# OpenProg-18F2550-new.net
KiCad netlist of a schematic drawn in EAGLE
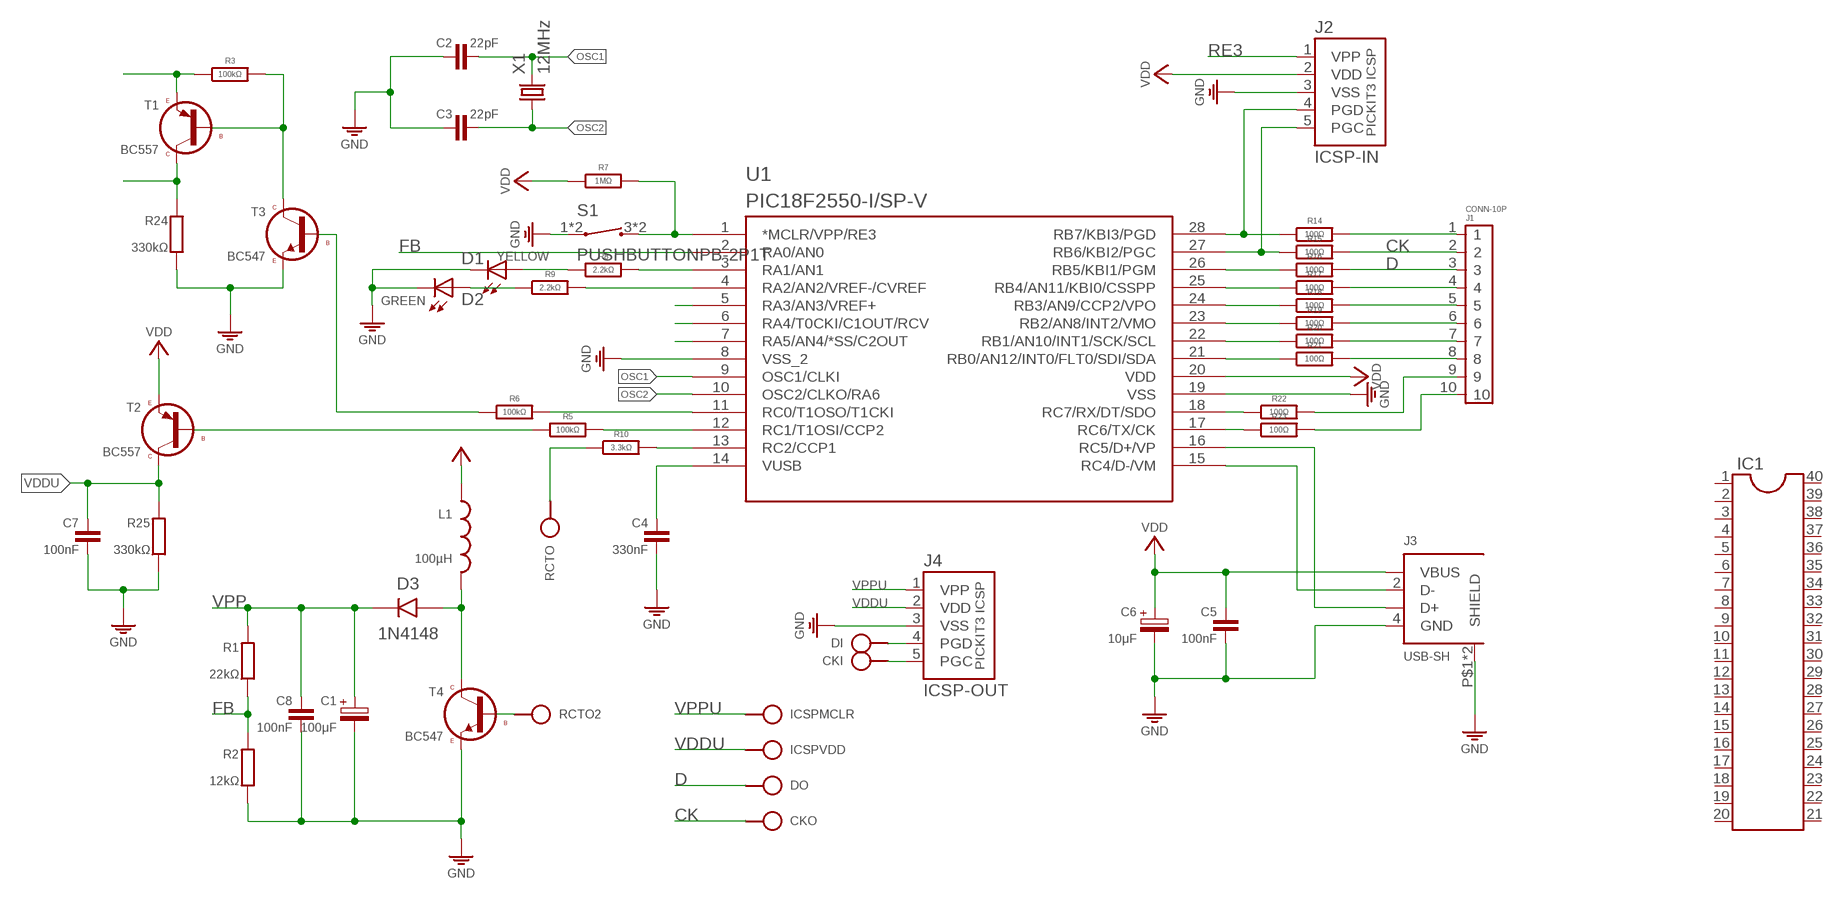
[diagram p0: schematic, sheet 1]

(export (version "E")
  (design (tool "Eeschema 10.0.6"))
  (components
    (comp (ref "C1")
      (value "100μF")
      (footprint "eagle-import:E2,5-5_V")
      (libsource (lib "eagle-import") (part "CPOLE2,5-5/V"))
    )
    (comp (ref "C2")
      (value "22pF")
      (footprint "eagle-import:C025-015X024")
      (libsource (lib "eagle-import") (part "C-H025-015X024"))
    )
    (comp (ref "C3")
      (value "22pF")
      (footprint "eagle-import:C025-015X024")
      (libsource (lib "eagle-import") (part "C-H025-015X024"))
    )
    (comp (ref "C4")
      (value "330nF")
      (footprint "eagle-import:C050-030X075")
      (libsource (lib "eagle-import") (part "C050-030X075"))
    )
    (comp (ref "C5")
      (value "100nF")
      (footprint "eagle-import:C025-015X024")
      (libsource (lib "eagle-import") (part "C025-015X024"))
    )
    (comp (ref "C6")
      (value "10μF")
      (footprint "eagle-import:E2,5-5")
      (libsource (lib "eagle-import") (part "CPOLE2.5-5"))
    )
    (comp (ref "C7")
      (value "100nF")
      (footprint "eagle-import:C025-015X024")
      (libsource (lib "eagle-import") (part "C025-015X024"))
    )
    (comp (ref "C8")
      (value "100nF")
      (footprint "eagle-import:C025-015X024")
      (libsource (lib "eagle-import") (part "C025-015X024"))
    )
    (comp (ref "CKI")
      (value "HPORT")
      (footprint "eagle-import:SPAD")
      (libsource (lib "eagle-import") (part "HPORT"))
    )
    (comp (ref "CKO")
      (value "HPORT")
      (footprint "eagle-import:SPAD")
      (libsource (lib "eagle-import") (part "HPORT"))
    )
    (comp (ref "D1")
      (value "YELLOW")
      (footprint "eagle-import:LED_3MM")
      (libsource (lib "eagle-import") (part "LED-3MM"))
    )
    (comp (ref "D2")
      (value "GREEN")
      (footprint "eagle-import:LED_3MM")
      (libsource (lib "eagle-import") (part "LED-3MM"))
    )
    (comp (ref "D3")
      (value "1N4148")
      (footprint "eagle-import:DO34-7")
      (libsource (lib "eagle-import") (part "1N4148-HDO34-7"))
    )
    (comp (ref "DI")
      (value "HPORT")
      (footprint "eagle-import:SPAD")
      (libsource (lib "eagle-import") (part "HPORT"))
    )
    (comp (ref "DO")
      (value "HPORT")
      (footprint "eagle-import:SPAD")
      (libsource (lib "eagle-import") (part "HPORT"))
    )
    (comp (ref "IC1")
      (value "DIL40")
      (footprint "eagle-import:DIL40")
      (libsource (lib "eagle-import") (part "DIL40"))
    )
    (comp (ref "ICSPMCLR")
      (value "HPORT")
      (footprint "eagle-import:SPAD")
      (libsource (lib "eagle-import") (part "HPORT"))
    )
    (comp (ref "ICSPVDD")
      (value "HPORT")
      (footprint "eagle-import:SPAD")
      (libsource (lib "eagle-import") (part "HPORT"))
    )
    (comp (ref "J1")
      (value "CONN-10P")
      (footprint "eagle-import:CONN-10P")
      (libsource (lib "eagle-import") (part "CONN-10P"))
    )
    (comp (ref "J2")
      (value "ICSP-IN")
      (footprint "eagle-import:PIC-PK3")
      (libsource (lib "eagle-import") (part "PICKIT3-ICSP-PK3"))
    )
    (comp (ref "J3")
      (value "USB-SH")
      (footprint "eagle-import:USB-B-PRINT")
      (libsource (lib "eagle-import") (part "USB-SH"))
    )
    (comp (ref "J4")
      (value "ICSP-OUT")
      (footprint "eagle-import:PIC-PK3")
      (libsource (lib "eagle-import") (part "PICKIT3-ICSP-PK3"))
    )
    (comp (ref "L1")
      (value "100µH")
      (footprint "eagle-import:L-03_10V")
      (libsource (lib "eagle-import") (part "L02/10"))
    )
    (comp (ref "R1")
      (value "22kΩ")
      (footprint "eagle-import:0204_10-V")
      (libsource (lib "eagle-import") (part "R0204/10-V"))
    )
    (comp (ref "R2")
      (value "12kΩ")
      (footprint "eagle-import:0204_10-V")
      (libsource (lib "eagle-import") (part "R0204/10-V"))
    )
    (comp (ref "R3")
      (value "100kΩ")
      (footprint "eagle-import:0204_2")
      (libsource (lib "eagle-import") (part "R-H0204/2"))
    )
    (comp (ref "R5")
      (value "100kΩ")
      (footprint "eagle-import:0204_10")
      (libsource (lib "eagle-import") (part "R-H0204/10"))
    )
    (comp (ref "R6")
      (value "100kΩ")
      (footprint "eagle-import:0204_10")
      (libsource (lib "eagle-import") (part "R-H0204/10"))
    )
    (comp (ref "R7")
      (value "1MΩ")
      (footprint "eagle-import:0204_10-V")
      (libsource (lib "eagle-import") (part "R-H0204/10-V"))
    )
    (comp (ref "R8")
      (value "2.2kΩ")
      (footprint "eagle-import:0204_10")
      (libsource (lib "eagle-import") (part "R-H0204/10"))
    )
    (comp (ref "R9")
      (value "2.2kΩ")
      (footprint "eagle-import:0204_10")
      (libsource (lib "eagle-import") (part "R-H0204/10"))
    )
    (comp (ref "R10")
      (value "3.3kΩ")
      (footprint "eagle-import:0204_10")
      (libsource (lib "eagle-import") (part "R-H0204/10"))
    )
    (comp (ref "R14")
      (value "100Ω")
      (footprint "eagle-import:0204_10")
      (libsource (lib "eagle-import") (part "R-H0204/10"))
    )
    (comp (ref "R15")
      (value "100Ω")
      (footprint "eagle-import:0204_10")
      (libsource (lib "eagle-import") (part "R-H0204/10"))
    )
    (comp (ref "R16")
      (value "100Ω")
      (footprint "eagle-import:0204_10")
      (libsource (lib "eagle-import") (part "R-H0204/10"))
    )
    (comp (ref "R17")
      (value "100Ω")
      (footprint "eagle-import:0204_10")
      (libsource (lib "eagle-import") (part "R-H0204/10"))
    )
    (comp (ref "R18")
      (value "100Ω")
      (footprint "eagle-import:0204_10")
      (libsource (lib "eagle-import") (part "R-H0204/10"))
    )
    (comp (ref "R19")
      (value "100Ω")
      (footprint "eagle-import:0204_10")
      (libsource (lib "eagle-import") (part "R-H0204/10"))
    )
    (comp (ref "R20")
      (value "100Ω")
      (footprint "eagle-import:0204_10")
      (libsource (lib "eagle-import") (part "R-H0204/10"))
    )
    (comp (ref "R21")
      (value "100Ω")
      (footprint "eagle-import:0204_10")
      (libsource (lib "eagle-import") (part "R-H0204/10"))
    )
    (comp (ref "R22")
      (value "100Ω")
      (footprint "eagle-import:0204_10")
      (libsource (lib "eagle-import") (part "R-H0204/10"))
    )
    (comp (ref "R23")
      (value "100Ω")
      (footprint "eagle-import:0204_10")
      (libsource (lib "eagle-import") (part "R-H0204/10"))
    )
    (comp (ref "R24")
      (value "330kΩ")
      (footprint "eagle-import:0204_10-V")
      (libsource (lib "eagle-import") (part "R0204/10-V"))
    )
    (comp (ref "R25")
      (value "330kΩ")
      (footprint "eagle-import:0204_10-V")
      (libsource (lib "eagle-import") (part "R0204/10-V"))
    )
    (comp (ref "RCTO")
      (value "HPORT")
      (footprint "eagle-import:SPAD")
      (libsource (lib "eagle-import") (part "HPORT"))
    )
    (comp (ref "RCTO2")
      (value "HPORT")
      (footprint "eagle-import:SPAD")
      (libsource (lib "eagle-import") (part "HPORT"))
    )
    (comp (ref "S1")
      (value "PUSHBUTTONPB-2P1T")
      (footprint "eagle-import:PB-2P1T")
      (libsource (lib "eagle-import") (part "PUSHBUTTONPB-2P1T"))
    )
    (comp (ref "T1")
      (value "BC557")
      (footprint "eagle-import:TO92-CBE")
      (libsource (lib "eagle-import") (part "BC557CBE"))
    )
    (comp (ref "T2")
      (value "BC557")
      (footprint "eagle-import:TO92-CBE")
      (libsource (lib "eagle-import") (part "BC557CBE"))
    )
    (comp (ref "T3")
      (value "BC547")
      (footprint "eagle-import:TO92")
      (libsource (lib "eagle-import") (part "BC547"))
    )
    (comp (ref "T4")
      (value "BC547")
      (footprint "eagle-import:TO92")
      (libsource (lib "eagle-import") (part "BC547"))
    )
    (comp (ref "U1")
      (value "PIC18F2550-I/SP-V")
      (footprint "eagle-import:DIL28-3_V")
      (libsource (lib "eagle-import") (part "PIC18F2550-I/SP-V"))
    )
    (comp (ref "X1")
      (value "12MHz")
      (footprint "eagle-import:HC49")
      (libsource (lib "eagle-import") (part "CRYSTALHC49"))
    )
  )
  (nets
    (net (code "1") (name "/CK") (class "Default")
      (node (ref "CKO") (pin "1") (pinfunction "P$1_1") (pintype "passive"))
      (node (ref "J1") (pin "2") (pinfunction "2_2") (pintype "passive"))
      (node (ref "R15") (pin "2") (pinfunction "2_2") (pintype "passive"))
    )
    (net (code "2") (name "/D") (class "Default")
      (node (ref "DO") (pin "1") (pinfunction "P$1_1") (pintype "passive"))
      (node (ref "J1") (pin "3") (pinfunction "3_3") (pintype "passive"))
      (node (ref "R16") (pin "2") (pinfunction "2_2") (pintype "passive"))
    )
    (net (code "3") (name "/FB") (class "Default")
      (node (ref "R1") (pin "2") (pinfunction "1_2") (pintype "passive"))
      (node (ref "R2") (pin "1") (pinfunction "2_1") (pintype "passive"))
      (node (ref "U1") (pin "2") (pinfunction "RA0/AN0_2") (pintype "passive"))
    )
    (net (code "4") (name "/RE3") (class "Default")
      (node (ref "J2") (pin "1") (pinfunction "VPP_1") (pintype "passive"))
      (node (ref "R7") (pin "2") (pinfunction "2_2") (pintype "passive"))
      (node (ref "S1") (pin "3") (pinfunction "2_3") (pintype "passive"))
      (node (ref "S1") (pin "4") (pinfunction "2_4") (pintype "passive"))
      (node (ref "U1") (pin "1") (pinfunction "*MCLR/VPP/RE3_1") (pintype "passive"))
    )
    (net (code "5") (name "/VPP") (class "Default")
      (node (ref "C1") (pin "+") (pinfunction "+_+") (pintype "passive"))
      (node (ref "C8") (pin "1") (pinfunction "1_1") (pintype "passive"))
      (node (ref "D3") (pin "C") (pinfunction "C_C") (pintype "passive"))
      (node (ref "R1") (pin "1") (pinfunction "2_1") (pintype "passive"))
      (node (ref "R3") (pin "1") (pinfunction "1_1") (pintype "passive"))
      (node (ref "T1") (pin "3") (pinfunction "E_3") (pintype "passive"))
    )
    (net (code "6") (name "/VPPU") (class "Default")
      (node (ref "ICSPMCLR") (pin "1") (pinfunction "P$1_1") (pintype "passive"))
      (node (ref "J4") (pin "1") (pinfunction "VPP_1") (pintype "passive"))
      (node (ref "R24") (pin "1") (pinfunction "2_1") (pintype "passive"))
      (node (ref "T1") (pin "1") (pinfunction "C_1") (pintype "passive"))
    )
    (net (code "7") (name "GND") (class "Default")
      (node (ref "C1") (pin "-") (pinfunction "-_-") (pintype "passive"))
      (node (ref "C2") (pin "1") (pinfunction "1_1") (pintype "passive"))
      (node (ref "C3") (pin "1") (pinfunction "1_1") (pintype "passive"))
      (node (ref "C4") (pin "2") (pinfunction "2_2") (pintype "passive"))
      (node (ref "C5") (pin "2") (pinfunction "2_2") (pintype "passive"))
      (node (ref "C6") (pin "-") (pinfunction "-_-") (pintype "passive"))
      (node (ref "C7") (pin "2") (pinfunction "2_2") (pintype "passive"))
      (node (ref "C8") (pin "2") (pinfunction "2_2") (pintype "passive"))
      (node (ref "D1") (pin "K") (pinfunction "C_K") (pintype "passive"))
      (node (ref "D2") (pin "K") (pinfunction "C_K") (pintype "passive"))
      (node (ref "J2") (pin "3") (pinfunction "VSS_3") (pintype "passive"))
      (node (ref "J3") (pin "4") (pinfunction "GND_4") (pintype "bidirectional"))
      (node (ref "J3") (pin "P$1") (pinfunction "SHIELD_P$1") (pintype "bidirectional"))
      (node (ref "J3") (pin "P$2") (pinfunction "SHIELD_P$2") (pintype "bidirectional"))
      (node (ref "J4") (pin "3") (pinfunction "VSS_3") (pintype "passive"))
      (node (ref "R2") (pin "2") (pinfunction "1_2") (pintype "passive"))
      (node (ref "R24") (pin "2") (pinfunction "1_2") (pintype "passive"))
      (node (ref "R25") (pin "2") (pinfunction "1_2") (pintype "passive"))
      (node (ref "S1") (pin "1") (pinfunction "1_1") (pintype "passive"))
      (node (ref "S1") (pin "2") (pinfunction "1_2") (pintype "passive"))
      (node (ref "T3") (pin "3") (pinfunction "E_3") (pintype "passive"))
      (node (ref "T4") (pin "3") (pinfunction "E_3") (pintype "passive"))
      (node (ref "U1") (pin "19") (pinfunction "VSS_19") (pintype "passive"))
      (node (ref "U1") (pin "8") (pinfunction "VSS_2_8") (pintype "passive"))
    )
    (net (code "8") (name "Net-(CKI-P$1)") (class "Default")
      (node (ref "CKI") (pin "1") (pinfunction "P$1_1") (pintype "passive"))
      (node (ref "J4") (pin "5") (pinfunction "PGC_5") (pintype "passive"))
    )
    (net (code "9") (name "Net-(D1-PadA)") (class "Default")
      (node (ref "D1") (pin "A") (pinfunction "A_A") (pintype "passive"))
      (node (ref "R8") (pin "1") (pinfunction "1_1") (pintype "passive"))
    )
    (net (code "10") (name "Net-(D2-PadA)") (class "Default")
      (node (ref "D2") (pin "A") (pinfunction "A_A") (pintype "passive"))
      (node (ref "R9") (pin "1") (pinfunction "1_1") (pintype "passive"))
    )
    (net (code "11") (name "Net-(DI-P$1)") (class "Default")
      (node (ref "DI") (pin "1") (pinfunction "P$1_1") (pintype "passive"))
      (node (ref "J4") (pin "4") (pinfunction "PGD_4") (pintype "passive"))
    )
    (net (code "12") (name "Net-(J1-Pad1)") (class "Default")
      (node (ref "J1") (pin "1") (pinfunction "1_1") (pintype "passive"))
      (node (ref "R14") (pin "2") (pinfunction "2_2") (pintype "passive"))
    )
    (net (code "13") (name "Net-(J1-Pad4)") (class "Default")
      (node (ref "J1") (pin "4") (pinfunction "4_4") (pintype "passive"))
      (node (ref "R17") (pin "2") (pinfunction "2_2") (pintype "passive"))
    )
    (net (code "14") (name "Net-(J1-Pad5)") (class "Default")
      (node (ref "J1") (pin "5") (pinfunction "5_5") (pintype "passive"))
      (node (ref "R18") (pin "2") (pinfunction "2_2") (pintype "passive"))
    )
    (net (code "15") (name "Net-(J1-Pad6)") (class "Default")
      (node (ref "J1") (pin "6") (pinfunction "6_6") (pintype "passive"))
      (node (ref "R19") (pin "2") (pinfunction "2_2") (pintype "passive"))
    )
    (net (code "16") (name "Net-(J1-Pad7)") (class "Default")
      (node (ref "J1") (pin "7") (pinfunction "7_7") (pintype "passive"))
      (node (ref "R20") (pin "2") (pinfunction "2_2") (pintype "passive"))
    )
    (net (code "17") (name "Net-(J1-Pad8)") (class "Default")
      (node (ref "J1") (pin "8") (pinfunction "8_8") (pintype "passive"))
      (node (ref "R21") (pin "2") (pinfunction "2_2") (pintype "passive"))
    )
    (net (code "18") (name "Net-(J1-Pad9)") (class "Default")
      (node (ref "J1") (pin "9") (pinfunction "9_9") (pintype "passive"))
      (node (ref "R22") (pin "2") (pinfunction "2_2") (pintype "passive"))
    )
    (net (code "19") (name "Net-(J1-Pad10)") (class "Default")
      (node (ref "J1") (pin "10") (pinfunction "10_10") (pintype "passive"))
      (node (ref "R23") (pin "2") (pinfunction "2_2") (pintype "passive"))
    )
    (net (code "20") (name "Net-(J2-PGC)") (class "Default")
      (node (ref "J2") (pin "5") (pinfunction "PGC_5") (pintype "passive"))
      (node (ref "R15") (pin "1") (pinfunction "1_1") (pintype "passive"))
      (node (ref "U1") (pin "27") (pinfunction "RB6/KBI2/PGC_27") (pintype "passive"))
    )
    (net (code "21") (name "Net-(J2-PGD)") (class "Default")
      (node (ref "J2") (pin "4") (pinfunction "PGD_4") (pintype "passive"))
      (node (ref "R14") (pin "1") (pinfunction "1_1") (pintype "passive"))
      (node (ref "U1") (pin "28") (pinfunction "RB7/KBI3/PGD_28") (pintype "passive"))
    )
    (net (code "22") (name "Net-(J3-D+)") (class "Default")
      (node (ref "J3") (pin "3") (pinfunction "D+_3") (pintype "bidirectional"))
      (node (ref "U1") (pin "16") (pinfunction "RC5/D+/VP_16") (pintype "passive"))
    )
    (net (code "23") (name "Net-(J3-D-)") (class "Default")
      (node (ref "J3") (pin "2") (pinfunction "D-_2") (pintype "bidirectional"))
      (node (ref "U1") (pin "15") (pinfunction "RC4/D-/VM_15") (pintype "passive"))
    )
    (net (code "24") (name "Net-(RCTO-P$1)") (class "Default")
      (node (ref "R10") (pin "1") (pinfunction "1_1") (pintype "passive"))
      (node (ref "RCTO") (pin "1") (pinfunction "P$1_1") (pintype "passive"))
    )
    (net (code "25") (name "Net-(RCTO2-P$1)") (class "Default")
      (node (ref "RCTO2") (pin "1") (pinfunction "P$1_1") (pintype "passive"))
      (node (ref "T4") (pin "2") (pinfunction "B_2") (pintype "passive"))
    )
    (net (code "26") (name "Net-(T1-B)") (class "Default")
      (node (ref "R3") (pin "2") (pinfunction "2_2") (pintype "passive"))
      (node (ref "T1") (pin "2") (pinfunction "B_2") (pintype "passive"))
      (node (ref "T3") (pin "1") (pinfunction "C_1") (pintype "passive"))
    )
    (net (code "27") (name "Net-(T2-B)") (class "Default")
      (node (ref "R5") (pin "1") (pinfunction "1_1") (pintype "passive"))
      (node (ref "T2") (pin "2") (pinfunction "B_2") (pintype "passive"))
    )
    (net (code "28") (name "Net-(T3-B)") (class "Default")
      (node (ref "R6") (pin "1") (pinfunction "1_1") (pintype "passive"))
      (node (ref "T3") (pin "2") (pinfunction "B_2") (pintype "passive"))
    )
    (net (code "29") (name "Net-(T4-C)") (class "Default")
      (node (ref "D3") (pin "A") (pinfunction "A_A") (pintype "passive"))
      (node (ref "L1") (pin "2") (pinfunction "2_2") (pintype "passive"))
      (node (ref "T4") (pin "1") (pinfunction "C_1") (pintype "passive"))
    )
    (net (code "30") (name "Net-(U1-RA1{slash}AN1)") (class "Default")
      (node (ref "R8") (pin "2") (pinfunction "2_2") (pintype "passive"))
      (node (ref "U1") (pin "3") (pinfunction "RA1/AN1_3") (pintype "passive"))
    )
    (net (code "31") (name "Net-(U1-RA2{slash}AN2{slash}VREF-{slash}CVREF)") (class "Default")
      (node (ref "R9") (pin "2") (pinfunction "2_2") (pintype "passive"))
      (node (ref "U1") (pin "4") (pinfunction "RA2/AN2/VREF-/CVREF_4") (pintype "passive"))
    )
    (net (code "32") (name "Net-(U1-RB0{slash}AN12{slash}INT0{slash}FLT0{slash}SDI{slash}SDA)") (class "Default")
      (node (ref "R21") (pin "1") (pinfunction "1_1") (pintype "passive"))
      (node (ref "U1") (pin "21") (pinfunction "RB0/AN12/INT0/FLT0/SDI/SDA_21") (pintype "passive"))
    )
    (net (code "33") (name "Net-(U1-RB1{slash}AN10{slash}INT1{slash}SCK{slash}SCL)") (class "Default")
      (node (ref "R20") (pin "1") (pinfunction "1_1") (pintype "passive"))
      (node (ref "U1") (pin "22") (pinfunction "RB1/AN10/INT1/SCK/SCL_22") (pintype "passive"))
    )
    (net (code "34") (name "Net-(U1-RB2{slash}AN8{slash}INT2{slash}VMO)") (class "Default")
      (node (ref "R19") (pin "1") (pinfunction "1_1") (pintype "passive"))
      (node (ref "U1") (pin "23") (pinfunction "RB2/AN8/INT2/VMO_23") (pintype "passive"))
    )
    (net (code "35") (name "Net-(U1-RB3{slash}AN9{slash}CCP2{slash}VPO)") (class "Default")
      (node (ref "R18") (pin "1") (pinfunction "1_1") (pintype "passive"))
      (node (ref "U1") (pin "24") (pinfunction "RB3/AN9/CCP2/VPO_24") (pintype "passive"))
    )
    (net (code "36") (name "Net-(U1-RB4{slash}AN11{slash}KBI0{slash}CSSPP)") (class "Default")
      (node (ref "R17") (pin "1") (pinfunction "1_1") (pintype "passive"))
      (node (ref "U1") (pin "25") (pinfunction "RB4/AN11/KBI0/CSSPP_25") (pintype "passive"))
    )
    (net (code "37") (name "Net-(U1-RB5{slash}KBI1{slash}PGM)") (class "Default")
      (node (ref "R16") (pin "1") (pinfunction "1_1") (pintype "passive"))
      (node (ref "U1") (pin "26") (pinfunction "RB5/KBI1/PGM_26") (pintype "passive"))
    )
    (net (code "38") (name "Net-(U1-RC0{slash}T1OSO{slash}T1CKI)") (class "Default")
      (node (ref "R6") (pin "2") (pinfunction "2_2") (pintype "passive"))
      (node (ref "U1") (pin "11") (pinfunction "RC0/T1OSO/T1CKI_11") (pintype "passive"))
    )
    (net (code "39") (name "Net-(U1-RC1{slash}T1OSI{slash}CCP2)") (class "Default")
      (node (ref "R5") (pin "2") (pinfunction "2_2") (pintype "passive"))
      (node (ref "U1") (pin "12") (pinfunction "RC1/T1OSI/CCP2_12") (pintype "passive"))
    )
    (net (code "40") (name "Net-(U1-RC2{slash}CCP1)") (class "Default")
      (node (ref "R10") (pin "2") (pinfunction "2_2") (pintype "passive"))
      (node (ref "U1") (pin "13") (pinfunction "RC2/CCP1_13") (pintype "passive"))
    )
    (net (code "41") (name "Net-(U1-RC6{slash}TX{slash}CK)") (class "Default")
      (node (ref "R23") (pin "1") (pinfunction "1_1") (pintype "passive"))
      (node (ref "U1") (pin "17") (pinfunction "RC6/TX/CK_17") (pintype "passive"))
    )
    (net (code "42") (name "Net-(U1-RC7{slash}RX{slash}DT{slash}SDO)") (class "Default")
      (node (ref "R22") (pin "1") (pinfunction "1_1") (pintype "passive"))
      (node (ref "U1") (pin "18") (pinfunction "RC7/RX/DT/SDO_18") (pintype "passive"))
    )
    (net (code "43") (name "Net-(U1-VUSB)") (class "Default")
      (node (ref "C4") (pin "1") (pinfunction "1_1") (pintype "passive"))
      (node (ref "U1") (pin "14") (pinfunction "VUSB_14") (pintype "passive"))
    )
    (net (code "44") (name "OSC1") (class "Default")
      (node (ref "C2") (pin "2") (pinfunction "2_2") (pintype "passive"))
      (node (ref "U1") (pin "9") (pinfunction "OSC1/CLKI_9") (pintype "passive"))
      (node (ref "X1") (pin "2") (pinfunction "2_2") (pintype "passive"))
    )
    (net (code "45") (name "OSC2") (class "Default")
      (node (ref "C3") (pin "2") (pinfunction "2_2") (pintype "passive"))
      (node (ref "U1") (pin "10") (pinfunction "OSC2/CLKO/RA6_10") (pintype "passive"))
      (node (ref "X1") (pin "1") (pinfunction "1_1") (pintype "passive"))
    )
    (net (code "46") (name "VDD") (class "Default")
      (node (ref "C5") (pin "1") (pinfunction "1_1") (pintype "passive"))
      (node (ref "C6") (pin "+") (pinfunction "+_+") (pintype "passive"))
      (node (ref "J2") (pin "2") (pinfunction "VDD_2") (pintype "passive"))
      (node (ref "J3") (pin "1") (pinfunction "VBUS_1") (pintype "bidirectional"))
      (node (ref "L1") (pin "1") (pinfunction "1_1") (pintype "passive"))
      (node (ref "R7") (pin "1") (pinfunction "1_1") (pintype "passive"))
      (node (ref "T2") (pin "3") (pinfunction "E_3") (pintype "passive"))
      (node (ref "U1") (pin "20") (pinfunction "VDD_20") (pintype "passive"))
    )
    (net (code "47") (name "VDDU") (class "Default")
      (node (ref "C7") (pin "1") (pinfunction "1_1") (pintype "passive"))
      (node (ref "ICSPVDD") (pin "1") (pinfunction "P$1_1") (pintype "passive"))
      (node (ref "J4") (pin "2") (pinfunction "VDD_2") (pintype "passive"))
      (node (ref "R25") (pin "1") (pinfunction "2_1") (pintype "passive"))
      (node (ref "T2") (pin "1") (pinfunction "C_1") (pintype "passive"))
    )
    (net (code "48") (name "unconnected-(IC1-Pad1)") (class "Default")
      (node (ref "IC1") (pin "1") (pinfunction "1_1") (pintype "passive"))
    )
    (net (code "49") (name "unconnected-(IC1-Pad2)") (class "Default")
      (node (ref "IC1") (pin "2") (pinfunction "2_2") (pintype "passive"))
    )
    (net (code "50") (name "unconnected-(IC1-Pad3)") (class "Default")
      (node (ref "IC1") (pin "3") (pinfunction "3_3") (pintype "passive"))
    )
    (net (code "51") (name "unconnected-(IC1-Pad4)") (class "Default")
      (node (ref "IC1") (pin "4") (pinfunction "4_4") (pintype "passive"))
    )
    (net (code "52") (name "unconnected-(IC1-Pad5)") (class "Default")
      (node (ref "IC1") (pin "5") (pinfunction "5_5") (pintype "passive"))
    )
    (net (code "53") (name "unconnected-(IC1-Pad6)") (class "Default")
      (node (ref "IC1") (pin "6") (pinfunction "6_6") (pintype "passive"))
    )
    (net (code "54") (name "unconnected-(IC1-Pad7)") (class "Default")
      (node (ref "IC1") (pin "7") (pinfunction "7_7") (pintype "passive"))
    )
    (net (code "55") (name "unconnected-(IC1-Pad8)") (class "Default")
      (node (ref "IC1") (pin "8") (pinfunction "8_8") (pintype "passive"))
    )
    (net (code "56") (name "unconnected-(IC1-Pad9)") (class "Default")
      (node (ref "IC1") (pin "9") (pinfunction "9_9") (pintype "passive"))
    )
    (net (code "57") (name "unconnected-(IC1-Pad10)") (class "Default")
      (node (ref "IC1") (pin "10") (pinfunction "10_10") (pintype "passive"))
    )
    (net (code "58") (name "unconnected-(IC1-Pad11)") (class "Default")
      (node (ref "IC1") (pin "11") (pinfunction "11_11") (pintype "passive"))
    )
    (net (code "59") (name "unconnected-(IC1-Pad12)") (class "Default")
      (node (ref "IC1") (pin "12") (pinfunction "12_12") (pintype "passive"))
    )
    (net (code "60") (name "unconnected-(IC1-Pad13)") (class "Default")
      (node (ref "IC1") (pin "13") (pinfunction "13_13") (pintype "passive"))
    )
    (net (code "61") (name "unconnected-(IC1-Pad14)") (class "Default")
      (node (ref "IC1") (pin "14") (pinfunction "14_14") (pintype "passive"))
    )
    (net (code "62") (name "unconnected-(IC1-Pad15)") (class "Default")
      (node (ref "IC1") (pin "15") (pinfunction "15_15") (pintype "passive"))
    )
    (net (code "63") (name "unconnected-(IC1-Pad16)") (class "Default")
      (node (ref "IC1") (pin "16") (pinfunction "16_16") (pintype "passive"))
    )
    (net (code "64") (name "unconnected-(IC1-Pad17)") (class "Default")
      (node (ref "IC1") (pin "17") (pinfunction "17_17") (pintype "passive"))
    )
    (net (code "65") (name "unconnected-(IC1-Pad18)") (class "Default")
      (node (ref "IC1") (pin "18") (pinfunction "18_18") (pintype "passive"))
    )
    (net (code "66") (name "unconnected-(IC1-Pad19)") (class "Default")
      (node (ref "IC1") (pin "19") (pinfunction "19_19") (pintype "passive"))
    )
    (net (code "67") (name "unconnected-(IC1-Pad20)") (class "Default")
      (node (ref "IC1") (pin "20") (pinfunction "20_20") (pintype "passive"))
    )
    (net (code "68") (name "unconnected-(IC1-Pad21)") (class "Default")
      (node (ref "IC1") (pin "21") (pinfunction "21_21") (pintype "passive"))
    )
    (net (code "69") (name "unconnected-(IC1-Pad22)") (class "Default")
      (node (ref "IC1") (pin "22") (pinfunction "22_22") (pintype "passive"))
    )
    (net (code "70") (name "unconnected-(IC1-Pad23)") (class "Default")
      (node (ref "IC1") (pin "23") (pinfunction "23_23") (pintype "passive"))
    )
    (net (code "71") (name "unconnected-(IC1-Pad24)") (class "Default")
      (node (ref "IC1") (pin "24") (pinfunction "24_24") (pintype "passive"))
    )
    (net (code "72") (name "unconnected-(IC1-Pad25)") (class "Default")
      (node (ref "IC1") (pin "25") (pinfunction "25_25") (pintype "passive"))
    )
    (net (code "73") (name "unconnected-(IC1-Pad26)") (class "Default")
      (node (ref "IC1") (pin "26") (pinfunction "26_26") (pintype "passive"))
    )
    (net (code "74") (name "unconnected-(IC1-Pad27)") (class "Default")
      (node (ref "IC1") (pin "27") (pinfunction "27_27") (pintype "passive"))
    )
    (net (code "75") (name "unconnected-(IC1-Pad28)") (class "Default")
      (node (ref "IC1") (pin "28") (pinfunction "28_28") (pintype "passive"))
    )
    (net (code "76") (name "unconnected-(IC1-Pad29)") (class "Default")
      (node (ref "IC1") (pin "29") (pinfunction "29_29") (pintype "passive"))
    )
    (net (code "77") (name "unconnected-(IC1-Pad30)") (class "Default")
      (node (ref "IC1") (pin "30") (pinfunction "30_30") (pintype "passive"))
    )
    (net (code "78") (name "unconnected-(IC1-Pad31)") (class "Default")
      (node (ref "IC1") (pin "31") (pinfunction "31_31") (pintype "passive"))
    )
    (net (code "79") (name "unconnected-(IC1-Pad32)") (class "Default")
      (node (ref "IC1") (pin "32") (pinfunction "32_32") (pintype "passive"))
    )
    (net (code "80") (name "unconnected-(IC1-Pad33)") (class "Default")
      (node (ref "IC1") (pin "33") (pinfunction "33_33") (pintype "passive"))
    )
    (net (code "81") (name "unconnected-(IC1-Pad34)") (class "Default")
      (node (ref "IC1") (pin "34") (pinfunction "34_34") (pintype "passive"))
    )
    (net (code "82") (name "unconnected-(IC1-Pad35)") (class "Default")
      (node (ref "IC1") (pin "35") (pinfunction "35_35") (pintype "passive"))
    )
    (net (code "83") (name "unconnected-(IC1-Pad36)") (class "Default")
      (node (ref "IC1") (pin "36") (pinfunction "36_36") (pintype "passive"))
    )
    (net (code "84") (name "unconnected-(IC1-Pad37)") (class "Default")
      (node (ref "IC1") (pin "37") (pinfunction "37_37") (pintype "passive"))
    )
    (net (code "85") (name "unconnected-(IC1-Pad38)") (class "Default")
      (node (ref "IC1") (pin "38") (pinfunction "38_38") (pintype "passive"))
    )
    (net (code "86") (name "unconnected-(IC1-Pad39)") (class "Default")
      (node (ref "IC1") (pin "39") (pinfunction "39_39") (pintype "passive"))
    )
    (net (code "87") (name "unconnected-(IC1-Pad40)") (class "Default")
      (node (ref "IC1") (pin "40") (pinfunction "40_40") (pintype "passive"))
    )
    (net (code "88") (name "unconnected-(U1-RA3{slash}AN3{slash}VREF+-Pad5)") (class "Default")
      (node (ref "U1") (pin "5") (pinfunction "RA3/AN3/VREF+_5") (pintype "passive"))
    )
    (net (code "89") (name "unconnected-(U1-RA4{slash}T0CKI{slash}C1OUT{slash}RCV-Pad6)") (class "Default")
      (node (ref "U1") (pin "6") (pinfunction "RA4/T0CKI/C1OUT/RCV_6") (pintype "passive"))
    )
    (net (code "90") (name "unconnected-(U1-RA5{slash}AN4{slash}*SS{slash}C2OUT-Pad7)") (class "Default")
      (node (ref "U1") (pin "7") (pinfunction "RA5/AN4/*SS/C2OUT_7") (pintype "passive"))
    )
  )
)
